# DRUM_1_CONTROL_8.net
KiCad netlist of a schematic drawn in EAGLE
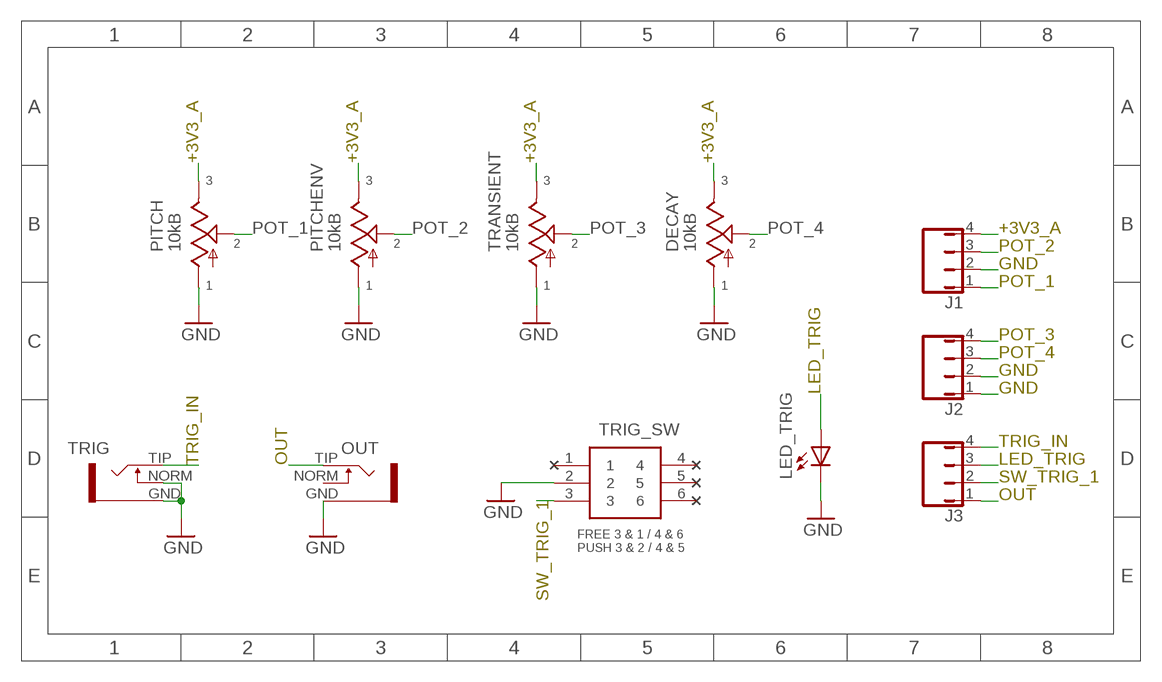
[diagram p0: schematic, sheet 1]

(export (version "E")
  (design (tool "Eeschema 10.0.6"))
  (components
    (comp (ref "DECAY")
      (value "10kB")
      (footprint "eagle-import:9MM_SNAP-IN_POT")
      (libsource (lib "eagle-import") (part "9MM_SNAP-IN_POT_"))
    )
    (comp (ref "J1")
      (value "1x4 FEMALE HEADER")
      (footprint "eagle-import:JMP_4P_SIP")
      (libsource (lib "eagle-import") (part "JMP/4P/SIP"))
    )
    (comp (ref "J2")
      (value "1x4 FEMALE HEADER")
      (footprint "eagle-import:JMP_4P_SIP")
      (libsource (lib "eagle-import") (part "JMP/4P/SIP"))
    )
    (comp (ref "J3")
      (value "1x4 FEMALE HEADER")
      (footprint "eagle-import:JMP_4P_SIP")
      (libsource (lib "eagle-import") (part "JMP/4P/SIP"))
    )
    (comp (ref "LED_TRIG")
      (value "LEDS3MM")
      (footprint "eagle-import:LED3MM")
      (libsource (lib "eagle-import") (part "LEDS3MM"))
    )
    (comp (ref "OUT")
      (value "THONKICONN")
      (footprint "eagle-import:INSTRUO_S_JACK_SMALL2")
      (libsource (lib "eagle-import") (part "THONKICONN"))
    )
    (comp (ref "PITCH")
      (value "10kB")
      (footprint "eagle-import:9MM_SNAP-IN_POT")
      (libsource (lib "eagle-import") (part "9MM_SNAP-IN_POT_"))
    )
    (comp (ref "PITCHENV")
      (value "10kB")
      (footprint "eagle-import:9MM_SNAP-IN_POT")
      (libsource (lib "eagle-import") (part "9MM_SNAP-IN_POT_"))
    )
    (comp (ref "TRANSIENT")
      (value "10kB")
      (footprint "eagle-import:9MM_SNAP-IN_POT")
      (libsource (lib "eagle-import") (part "9MM_SNAP-IN_POT_"))
    )
    (comp (ref "TRIG")
      (value "THONKICONN")
      (footprint "eagle-import:INSTRUO_S_JACK_SMALL2")
      (libsource (lib "eagle-import") (part "THONKICONN"))
    )
    (comp (ref "TRIG_SW")
      (value "GPBS-800L 8MM MOMENTARY")
      (footprint "eagle-import:GPBS800L")
      (fields
        (field (name "MANUFACTURER_PART_NUMBER") "GPBS-800L")
        (field (name "MOUSER_PART_NUMBER") "629-GPBS-800L")
      )
      (libsource (lib "eagle-import") (part "GPBS-800L"))
    )
  )
  (nets
    (net (code "1") (name "/+3V3_A") (class "Default")
      (node (ref "DECAY") (pin "3") (pinfunction "E_3") (pintype "passive"))
      (node (ref "J1") (pin "4") (pinfunction "4_4") (pintype "passive"))
      (node (ref "PITCH") (pin "3") (pinfunction "E_3") (pintype "passive"))
      (node (ref "PITCHENV") (pin "3") (pinfunction "E_3") (pintype "passive"))
      (node (ref "TRANSIENT") (pin "3") (pinfunction "E_3") (pintype "passive"))
    )
    (net (code "2") (name "/LED_TRIG") (class "Default")
      (node (ref "J3") (pin "3") (pinfunction "3_3") (pintype "passive"))
      (node (ref "LED_TRIG") (pin "A") (pinfunction "A_A") (pintype "passive"))
    )
    (net (code "3") (name "/OUT") (class "Default")
      (node (ref "J3") (pin "1") (pinfunction "1_1") (pintype "passive"))
      (node (ref "OUT") (pin "TIP") (pinfunction "TIP_TIP") (pintype "passive"))
    )
    (net (code "4") (name "/POT_1") (class "Default")
      (node (ref "J1") (pin "1") (pinfunction "1_1") (pintype "passive"))
      (node (ref "PITCH") (pin "2") (pinfunction "S_2") (pintype "passive"))
    )
    (net (code "5") (name "/POT_2") (class "Default")
      (node (ref "J1") (pin "3") (pinfunction "3_3") (pintype "passive"))
      (node (ref "PITCHENV") (pin "2") (pinfunction "S_2") (pintype "passive"))
    )
    (net (code "6") (name "/POT_3") (class "Default")
      (node (ref "J2") (pin "4") (pinfunction "4_4") (pintype "passive"))
      (node (ref "TRANSIENT") (pin "2") (pinfunction "S_2") (pintype "passive"))
    )
    (net (code "7") (name "/POT_4") (class "Default")
      (node (ref "DECAY") (pin "2") (pinfunction "S_2") (pintype "passive"))
      (node (ref "J2") (pin "3") (pinfunction "3_3") (pintype "passive"))
    )
    (net (code "8") (name "/SW_TRIG_1") (class "Default")
      (node (ref "J3") (pin "2") (pinfunction "2_2") (pintype "passive"))
      (node (ref "TRIG_SW") (pin "3") (pinfunction "3_3") (pintype "bidirectional"))
    )
    (net (code "9") (name "/TRIG_IN") (class "Default")
      (node (ref "J3") (pin "4") (pinfunction "4_4") (pintype "passive"))
      (node (ref "TRIG") (pin "TIP") (pinfunction "TIP_TIP") (pintype "passive"))
    )
    (net (code "10") (name "GND") (class "Default")
      (node (ref "DECAY") (pin "1") (pinfunction "A_1") (pintype "passive"))
      (node (ref "J1") (pin "2") (pinfunction "2_2") (pintype "passive"))
      (node (ref "J2") (pin "1") (pinfunction "1_1") (pintype "passive"))
      (node (ref "J2") (pin "2") (pinfunction "2_2") (pintype "passive"))
      (node (ref "LED_TRIG") (pin "K") (pinfunction "C_K") (pintype "passive"))
      (node (ref "OUT") (pin "GND") (pinfunction "GND_GND") (pintype "passive"))
      (node (ref "PITCH") (pin "1") (pinfunction "A_1") (pintype "passive"))
      (node (ref "PITCHENV") (pin "1") (pinfunction "A_1") (pintype "passive"))
      (node (ref "TRANSIENT") (pin "1") (pinfunction "A_1") (pintype "passive"))
      (node (ref "TRIG") (pin "GND") (pinfunction "GND_GND") (pintype "passive"))
      (node (ref "TRIG") (pin "NORM") (pinfunction "NORM_NORM") (pintype "passive"))
      (node (ref "TRIG_SW") (pin "2") (pinfunction "2_2") (pintype "bidirectional"))
    )
    (net (code "11") (name "unconnected-(OUT-PadNORM)") (class "Default")
      (node (ref "OUT") (pin "NORM") (pinfunction "NORM_NORM") (pintype "passive"))
    )
    (net (code "12") (name "unconnected-(TRIG_SW-Pad1)") (class "Default")
      (node (ref "TRIG_SW") (pin "1") (pinfunction "1_1") (pintype "bidirectional"))
    )
    (net (code "13") (name "unconnected-(TRIG_SW-Pad4)") (class "Default")
      (node (ref "TRIG_SW") (pin "4") (pinfunction "4_4") (pintype "bidirectional"))
    )
    (net (code "14") (name "unconnected-(TRIG_SW-Pad5)") (class "Default")
      (node (ref "TRIG_SW") (pin "5") (pinfunction "5_5") (pintype "bidirectional"))
    )
    (net (code "15") (name "unconnected-(TRIG_SW-Pad6)") (class "Default")
      (node (ref "TRIG_SW") (pin "6") (pinfunction "6_6") (pintype "bidirectional"))
    )
  )
)
